# PCI_Express_Connectors.net
KiCad netlist of a schematic drawn in Altium Designer
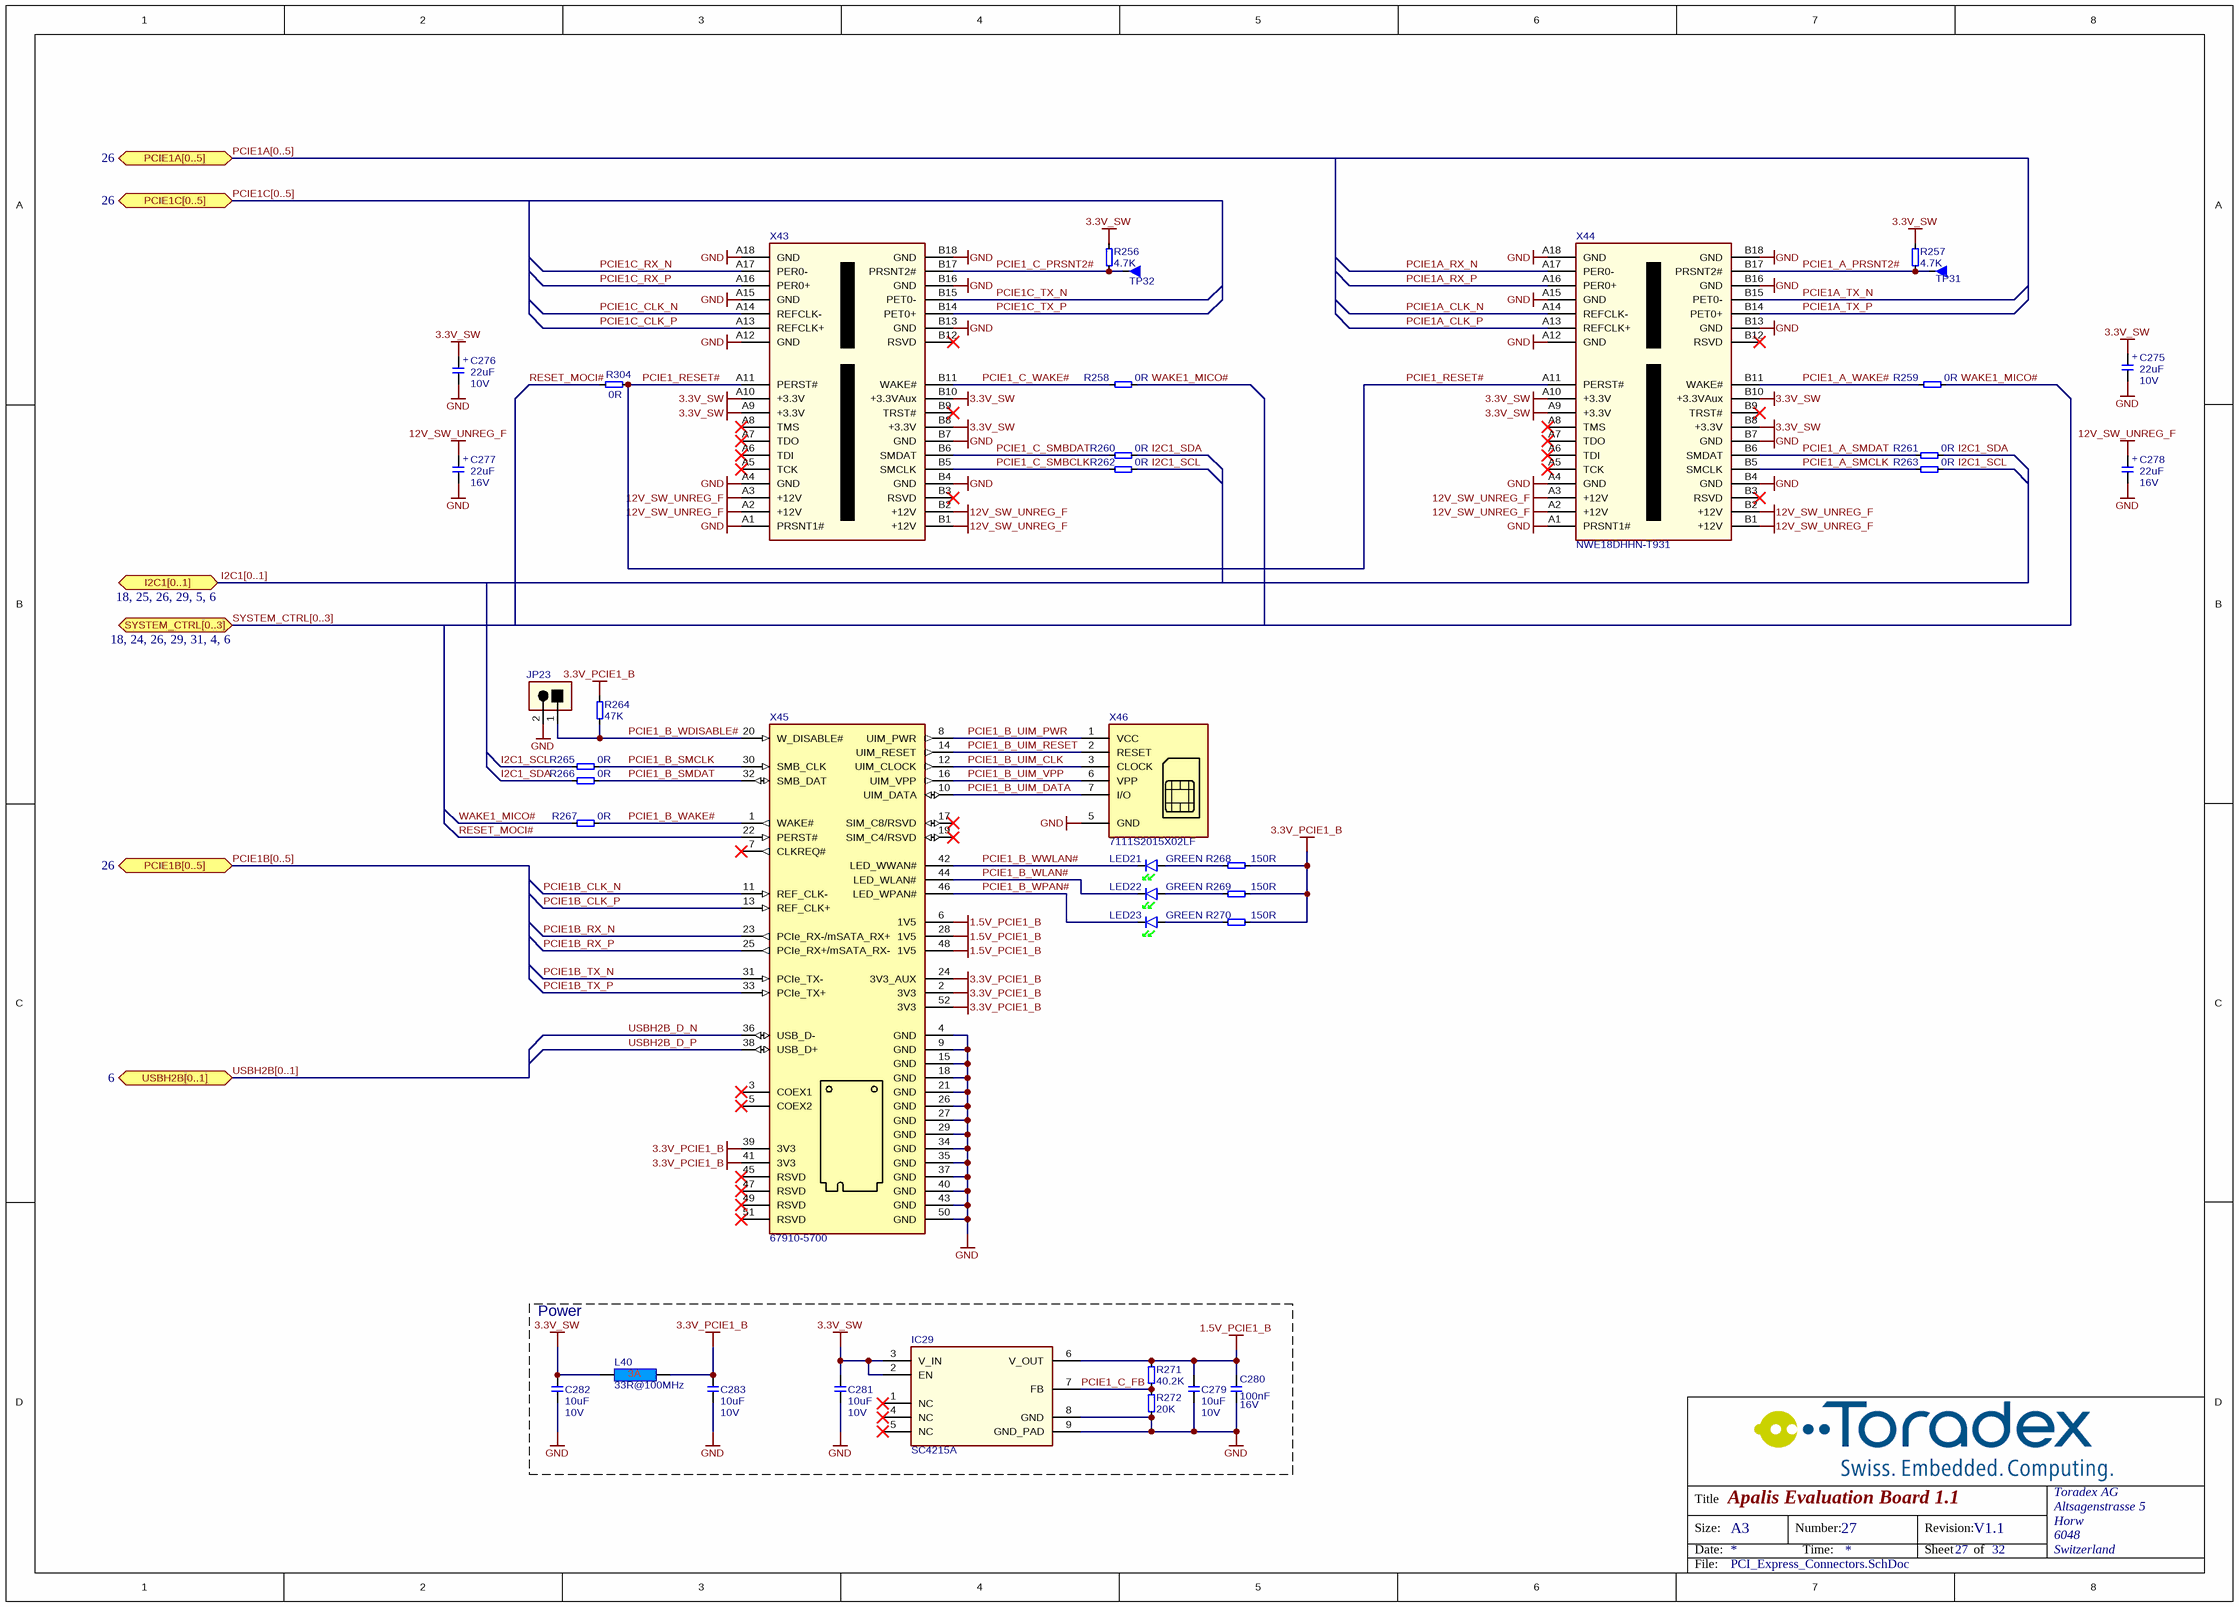
[diagram p0: PCI_Express_Connectors.SchDoc]

(export (version "E")
  (design (tool "Eeschema 10.0.6"))
  (components
    (comp (ref "C275")
      (value "22uF")
      (footprint "CAPMP3528X210N")
      (description "Capacitor TA 22uF 10V 20% 3528")
      (fields (field (name "TOLERANCE") "20%") (field (name "RATING") "10V"))
      (libsource (lib "Apalis Evaluation Board") (part "C-TA-22uF-10V-20%-3528"))
    )
    (comp (ref "C276")
      (value "22uF")
      (footprint "CAPMP3528X210N")
      (description "Capacitor TA 22uF 10V 20% 3528")
      (fields (field (name "TOLERANCE") "20%") (field (name "RATING") "10V"))
      (libsource (lib "Apalis Evaluation Board") (part "C-TA-22uF-10V-20%-3528"))
    )
    (comp (ref "C277")
      (value "22uF")
      (footprint "CAPMP3528X210N")
      (description "Capacitor TA 22uF 16V 20% 3528")
      (fields (field (name "TOLERANCE") "20%") (field (name "RATING") "16V"))
      (libsource (lib "Apalis Evaluation Board") (part "C-TA-22uF-16V-20%-3528"))
    )
    (comp (ref "C278")
      (value "22uF")
      (footprint "CAPMP3528X210N")
      (description "Capacitor TA 22uF 16V 20% 3528")
      (fields (field (name "TOLERANCE") "20%") (field (name "RATING") "16V"))
      (libsource (lib "Apalis Evaluation Board") (part "C-TA-22uF-16V-20%-3528"))
    )
    (comp (ref "C279")
      (value "10uF")
      (footprint "T_CAPC0603X33N")
      (description "Capacitor Ceramic X5R 10uF 10V 20% 0603")
      (fields (field (name "TOLERANCE") "20%") (field (name "RATING") "10V"))
      (libsource (lib "Apalis Evaluation Board") (part "C-X5R-10uF-10V-20%-0603"))
    )
    (comp (ref "C280")
      (value "100nF")
      (footprint "T_CAPC0603X33N")
      (description "Capacitor Ceramic X7R 100nF 16V 10% 0603")
      (fields (field (name "TOLERANCE") "10%") (field (name "RATING") "16V"))
      (libsource (lib "Apalis Evaluation Board") (part "C-X7R-100nF-16V-10%-0603"))
    )
    (comp (ref "C281")
      (value "10uF")
      (footprint "T_CAPC0603X33N")
      (description "Capacitor Ceramic X5R 10uF 10V 20% 0603")
      (fields (field (name "TOLERANCE") "20%") (field (name "RATING") "10V"))
      (libsource (lib "Apalis Evaluation Board") (part "C-X5R-10uF-10V-20%-0603"))
    )
    (comp (ref "C282")
      (value "10uF")
      (footprint "T_CAPC0603X33N")
      (description "Capacitor Ceramic X5R 10uF 10V 20% 0603")
      (fields (field (name "TOLERANCE") "20%") (field (name "RATING") "10V"))
      (libsource (lib "Apalis Evaluation Board") (part "C-X5R-10uF-10V-20%-0603"))
    )
    (comp (ref "C283")
      (value "10uF")
      (footprint "T_CAPC0603X33N")
      (description "Capacitor Ceramic X5R 10uF 10V 20% 0603")
      (fields (field (name "TOLERANCE") "20%") (field (name "RATING") "10V"))
      (libsource (lib "Apalis Evaluation Board") (part "C-X5R-10uF-10V-20%-0603"))
    )
    (comp (ref "IC29")
      (value "IC-Semtech-SC4215A")
      (footprint "SOIC127P650X175_HS-8N")
      (description "LDO TO 2A")
      (fields (field (name "PART NO.") "SC4215A"))
      (libsource (lib "Apalis Evaluation Board") (part "IC-Semtech-SC4215A"))
    )
    (comp (ref "JP23")
      (value "TSW-101-07-G-D")
      (footprint "T_Samtec_TSW-101-07-G-D")
      (description "Header male, 1x2 Pins, 2.54 mm pitch")
      (libsource (lib "Apalis Evaluation Board") (part "CON-Samtec-TSW-101-07-G-D"))
    )
    (comp (ref "L40")
      (value "33R@100MHz")
      (footprint "INDC1608X95N")
      (description "33R@100MHz 3A EMI FILTER")
      (fields (field (name "TOLERANCE") "25%"))
      (libsource (lib "Apalis Evaluation Board") (part "L-33R@100MHz-3A-25%-0603"))
    )
    (comp (ref "LED21")
      (value "LG T670-K1L2-1")
      (footprint "T_Osram_T670_GREEN")
      (description "LED green Osram LG T670-K1L2-1")
      (fields (field (name "COLOR") "GREEN"))
      (libsource (lib "Apalis Evaluation Board") (part "LED-Osram-T670-K1L2-1"))
    )
    (comp (ref "LED22")
      (value "LG T670-K1L2-1")
      (footprint "T_Osram_T670_GREEN")
      (description "LED green Osram LG T670-K1L2-1")
      (fields (field (name "COLOR") "GREEN"))
      (libsource (lib "Apalis Evaluation Board") (part "LED-Osram-T670-K1L2-1"))
    )
    (comp (ref "LED23")
      (value "LG T670-K1L2-1")
      (footprint "T_Osram_T670_GREEN")
      (description "LED green Osram LG T670-K1L2-1")
      (fields (field (name "COLOR") "GREEN"))
      (libsource (lib "Apalis Evaluation Board") (part "LED-Osram-T670-K1L2-1"))
    )
    (comp (ref "R256")
      (value "4.7K")
      (footprint "t_RESC0603X30N")
      (description "Resistor 4.7 Kohm 63mW 5% 0603")
      (fields (field (name "TOLERANCE") "5%"))
      (libsource (lib "Apalis Evaluation Board") (part "R-4.7kR-63mW-5%-0603"))
    )
    (comp (ref "R257")
      (value "4.7K")
      (footprint "t_RESC0603X30N")
      (description "Resistor 4.7 Kohm 63mW 5% 0603")
      (fields (field (name "TOLERANCE") "5%"))
      (libsource (lib "Apalis Evaluation Board") (part "R-4.7kR-63mW-5%-0603"))
    )
    (comp (ref "R258")
      (value "0R")
      (footprint "T_RESC0603X30N")
      (description "Resistor 0 ohm 63mW 1% 0603")
      (fields (field (name "TOLERANCE") "1%"))
      (libsource (lib "Apalis Evaluation Board") (part "R-0R-63mW-1%-0603"))
    )
    (comp (ref "R259")
      (value "0R")
      (footprint "T_RESC0603X30N")
      (description "Resistor 0 ohm 63mW 1% 0603")
      (fields (field (name "TOLERANCE") "1%"))
      (libsource (lib "Apalis Evaluation Board") (part "R-0R-63mW-1%-0603"))
    )
    (comp (ref "R260")
      (value "0R")
      (footprint "T_RESC0603X30N")
      (description "Resistor 0 ohm 63mW 1% 0603")
      (fields (field (name "TOLERANCE") "1%"))
      (libsource (lib "Apalis Evaluation Board") (part "R-0R-63mW-1%-0603"))
    )
    (comp (ref "R261")
      (value "0R")
      (footprint "T_RESC0603X30N")
      (description "Resistor 0 ohm 63mW 1% 0603")
      (fields (field (name "TOLERANCE") "1%"))
      (libsource (lib "Apalis Evaluation Board") (part "R-0R-63mW-1%-0603"))
    )
    (comp (ref "R262")
      (value "0R")
      (footprint "T_RESC0603X30N")
      (description "Resistor 0 ohm 63mW 1% 0603")
      (fields (field (name "TOLERANCE") "1%"))
      (libsource (lib "Apalis Evaluation Board") (part "R-0R-63mW-1%-0603"))
    )
    (comp (ref "R263")
      (value "0R")
      (footprint "T_RESC0603X30N")
      (description "Resistor 0 ohm 63mW 1% 0603")
      (fields (field (name "TOLERANCE") "1%"))
      (libsource (lib "Apalis Evaluation Board") (part "R-0R-63mW-1%-0603"))
    )
    (comp (ref "R264")
      (value "47K")
      (footprint "T_RESC0603X30N")
      (description "Resistor 47 Kohm 63mW 5% 0603")
      (fields (field (name "TOLERANCE") "5%"))
      (libsource (lib "Apalis Evaluation Board") (part "R-47KR-63mW-5%-0603"))
    )
    (comp (ref "R265")
      (value "0R")
      (footprint "T_RESC0603X30N")
      (description "Resistor 0 ohm 63mW 1% 0603")
      (fields (field (name "TOLERANCE") "1%"))
      (libsource (lib "Apalis Evaluation Board") (part "R-0R-63mW-1%-0603"))
    )
    (comp (ref "R266")
      (value "0R")
      (footprint "T_RESC0603X30N")
      (description "Resistor 0 ohm 63mW 1% 0603")
      (fields (field (name "TOLERANCE") "1%"))
      (libsource (lib "Apalis Evaluation Board") (part "R-0R-63mW-1%-0603"))
    )
    (comp (ref "R267")
      (value "0R")
      (footprint "T_RESC0603X30N")
      (description "Resistor 0 ohm 63mW 1% 0603")
      (fields (field (name "TOLERANCE") "1%"))
      (libsource (lib "Apalis Evaluation Board") (part "R-0R-63mW-1%-0603"))
    )
    (comp (ref "R268")
      (value "150R")
      (footprint "T_RESC0603X30N")
      (description "Resistor 150 ohm 63mW 1% 0603")
      (fields (field (name "TOLERANCE") "1%"))
      (libsource (lib "Apalis Evaluation Board") (part "R-150R-63mW-1%-0603"))
    )
    (comp (ref "R269")
      (value "150R")
      (footprint "T_RESC0603X30N")
      (description "Resistor 150 ohm 63mW 1% 0603")
      (fields (field (name "TOLERANCE") "1%"))
      (libsource (lib "Apalis Evaluation Board") (part "R-150R-63mW-1%-0603"))
    )
    (comp (ref "R270")
      (value "150R")
      (footprint "T_RESC0603X30N")
      (description "Resistor 150 ohm 63mW 1% 0603")
      (fields (field (name "TOLERANCE") "1%"))
      (libsource (lib "Apalis Evaluation Board") (part "R-150R-63mW-1%-0603"))
    )
    (comp (ref "R271")
      (value "40.2K")
      (footprint "T_RESC0603X30N")
      (description "Resistor 40.2 Kohm 63mW 1% 0603")
      (fields (field (name "TOLERANCE") "1%"))
      (libsource (lib "Apalis Evaluation Board") (part "R-40.2KR-63mW-1%-0603"))
    )
    (comp (ref "R272")
      (value "20K")
      (footprint "T_RESC0603X30N")
      (description "Resistor 20 Kohm 63mW 1% 0603")
      (fields (field (name "TOLERANCE") "1%"))
      (libsource (lib "Apalis Evaluation Board") (part "R-20KR-63mW-1%-0603"))
    )
    (comp (ref "R304")
      (value "0R")
      (footprint "T_RESC0603X30N")
      (description "Resistor 0 ohm 63mW 1% 0603")
      (fields (field (name "TOLERANCE") "1%"))
      (libsource (lib "Apalis Evaluation Board") (part "R-0R-63mW-1%-0603"))
    )
    (comp (ref "TP31")
      (value "Testpin")
      (footprint "T_TP-THT")
      (description "Testpin TH")
      (libsource (lib "Apalis Evaluation Board") (part "Testpin"))
    )
    (comp (ref "TP32")
      (value "Testpin")
      (footprint "T_TP-THT")
      (description "Testpin TH")
      (libsource (lib "Apalis Evaluation Board") (part "Testpin"))
    )
    (comp (ref "X43")
      (value "NWE18DHHN-T931")
      (footprint "T_Sullins_NWE18DHHN-T931")
      (description "PCI EXPRESS 36POS")
      (libsource (lib "") (part "CON-Sullins-NWE18DHHN-T931_1"))
    )
    (comp (ref "X44")
      (value "NWE18DHHN-T931")
      (footprint "T_Sullins_NWE18DHHN-T931")
      (description "PCI EXPRESS 36POS")
      (fields (field (name "MANUFACTURER PART NO.") "NWE18DHHN-T931"))
      (libsource (lib "Apalis Evaluation Board") (part "CON-Sullins-NWE18DHHN-T931"))
    )
    (comp (ref "X45")
      (value "67910-5700")
      (footprint "T_Molex_67910-5700")
      (description "PCIe_Mini Card Holder")
      (fields (field (name "PART NO.") "67910-5700"))
      (libsource (lib "Apalis Evaluation Board") (part "CON-Molex-67910-5700"))
    )
    (comp (ref "X46")
      (value "7111S2015X02LF")
      (footprint "T_FCI_7111S2015X02LF")
      (description "6 Contacts Sim Card Holder")
      (fields (field (name "PART NO.") "7111S2015X02LF"))
      (libsource (lib "Apalis Evaluation Board") (part "CON-FCI-7111S2015X02LF"))
    )
  )
  (nets
    (net (code "28") (name "/I2C1_SCL") (class "Default")
      (node (ref "R262") (pin "2") (pinfunction "2_2") (pintype "passive"))
      (node (ref "R263") (pin "2") (pinfunction "2_2") (pintype "passive"))
      (node (ref "R265") (pin "1") (pinfunction "1_1") (pintype "passive"))
    )
    (net (code "29") (name "/I2C1_SDA") (class "Default")
      (node (ref "R260") (pin "2") (pinfunction "2_2") (pintype "passive"))
      (node (ref "R261") (pin "2") (pinfunction "2_2") (pintype "passive"))
      (node (ref "R266") (pin "1") (pinfunction "1_1") (pintype "passive"))
    )
    (net (code "31") (name "/PCIE1A_CLK_N") (class "Default")
      (node (ref "X44") (pin "A14") (pinfunction "REFCLK-_A14") (pintype "passive"))
    )
    (net (code "32") (name "/PCIE1A_CLK_P") (class "Default")
      (node (ref "X44") (pin "A13") (pinfunction "REFCLK+_A13") (pintype "passive"))
    )
    (net (code "33") (name "/PCIE1A_RX_N") (class "Default")
      (node (ref "X44") (pin "A17") (pinfunction "PER0-_A17") (pintype "passive"))
    )
    (net (code "34") (name "/PCIE1A_RX_P") (class "Default")
      (node (ref "X44") (pin "A16") (pinfunction "PER0+_A16") (pintype "passive"))
    )
    (net (code "35") (name "/PCIE1A_TX_N") (class "Default")
      (node (ref "X44") (pin "B15") (pinfunction "PET0-_B15") (pintype "passive"))
    )
    (net (code "36") (name "/PCIE1A_TX_P") (class "Default")
      (node (ref "X44") (pin "B14") (pinfunction "PET0+_B14") (pintype "passive"))
    )
    (net (code "38") (name "/PCIE1B_CLK_N") (class "Default")
      (node (ref "X45") (pin "11") (pinfunction "REF_CLK-_11") (pintype "input"))
    )
    (net (code "39") (name "/PCIE1B_CLK_P") (class "Default")
      (node (ref "X45") (pin "13") (pinfunction "REF_CLK+_13") (pintype "input"))
    )
    (net (code "40") (name "/PCIE1B_RX_N") (class "Default")
      (node (ref "X45") (pin "23") (pinfunction "PCIe_RX-/mSATA_RX+_23") (pintype "output"))
    )
    (net (code "41") (name "/PCIE1B_RX_P") (class "Default")
      (node (ref "X45") (pin "25") (pinfunction "PCIe_RX+/mSATA_RX-_25") (pintype "output"))
    )
    (net (code "42") (name "/PCIE1B_TX_N") (class "Default")
      (node (ref "X45") (pin "31") (pinfunction "PCIe_TX-_31") (pintype "input"))
    )
    (net (code "43") (name "/PCIE1B_TX_P") (class "Default")
      (node (ref "X45") (pin "33") (pinfunction "PCIe_TX+_33") (pintype "input"))
    )
    (net (code "45") (name "/PCIE1C_CLK_N") (class "Default")
      (node (ref "X43") (pin "A14") (pinfunction "REFCLK-_A14") (pintype "passive"))
    )
    (net (code "46") (name "/PCIE1C_CLK_P") (class "Default")
      (node (ref "X43") (pin "A13") (pinfunction "REFCLK+_A13") (pintype "passive"))
    )
    (net (code "47") (name "/PCIE1C_RX_N") (class "Default")
      (node (ref "X43") (pin "A17") (pinfunction "PER0-_A17") (pintype "passive"))
    )
    (net (code "48") (name "/PCIE1C_RX_P") (class "Default")
      (node (ref "X43") (pin "A16") (pinfunction "PER0+_A16") (pintype "passive"))
    )
    (net (code "49") (name "/PCIE1C_TX_N") (class "Default")
      (node (ref "X43") (pin "B15") (pinfunction "PET0-_B15") (pintype "passive"))
    )
    (net (code "50") (name "/PCIE1C_TX_P") (class "Default")
      (node (ref "X43") (pin "B14") (pinfunction "PET0+_B14") (pintype "passive"))
    )
    (net (code "51") (name "/PCIE1_A_PRSNT2#") (class "Default")
      (node (ref "R257") (pin "1") (pinfunction "1_1") (pintype "passive"))
      (node (ref "TP31") (pin "1") (pinfunction "1_1") (pintype "passive"))
      (node (ref "X44") (pin "B17") (pinfunction "PRSNT2#_B17") (pintype "passive"))
    )
    (net (code "52") (name "/PCIE1_A_SMCLK") (class "Default")
      (node (ref "R263") (pin "1") (pinfunction "1_1") (pintype "passive"))
      (node (ref "X44") (pin "B5") (pinfunction "SMCLK_B5") (pintype "passive"))
    )
    (net (code "53") (name "/PCIE1_A_SMDAT") (class "Default")
      (node (ref "R261") (pin "1") (pinfunction "1_1") (pintype "passive"))
      (node (ref "X44") (pin "B6") (pinfunction "SMDAT_B6") (pintype "passive"))
    )
    (net (code "54") (name "/PCIE1_A_WAKE#") (class "Default")
      (node (ref "R259") (pin "1") (pinfunction "1_1") (pintype "passive"))
      (node (ref "X44") (pin "B11") (pinfunction "WAKE#_B11") (pintype "passive"))
    )
    (net (code "55") (name "/PCIE1_B_SMCLK") (class "Default")
      (node (ref "R265") (pin "2") (pinfunction "2_2") (pintype "passive"))
      (node (ref "X45") (pin "30") (pinfunction "SMB_CLK_30") (pintype "input"))
    )
    (net (code "56") (name "/PCIE1_B_SMDAT") (class "Default")
      (node (ref "R266") (pin "2") (pinfunction "2_2") (pintype "passive"))
      (node (ref "X45") (pin "32") (pinfunction "SMB_DAT_32") (pintype "bidirectional"))
    )
    (net (code "57") (name "/PCIE1_B_UIM_CLK") (class "Default")
      (node (ref "X45") (pin "12") (pinfunction "UIM_CLOCK_12") (pintype "output"))
      (node (ref "X46") (pin "3") (pinfunction "CLOCK_3") (pintype "passive"))
    )
    (net (code "58") (name "/PCIE1_B_UIM_DATA") (class "Default")
      (node (ref "X45") (pin "10") (pinfunction "UIM_DATA_10") (pintype "bidirectional"))
      (node (ref "X46") (pin "7") (pinfunction "I/O_7") (pintype "passive"))
    )
    (net (code "59") (name "/PCIE1_B_UIM_PWR") (class "Default")
      (node (ref "X45") (pin "8") (pinfunction "UIM_PWR_8") (pintype "output"))
      (node (ref "X46") (pin "1") (pinfunction "VCC_1") (pintype "passive"))
    )
    (net (code "60") (name "/PCIE1_B_UIM_RESET") (class "Default")
      (node (ref "X45") (pin "14") (pinfunction "UIM_RESET_14") (pintype "output"))
      (node (ref "X46") (pin "2") (pinfunction "RESET_2") (pintype "passive"))
    )
    (net (code "61") (name "/PCIE1_B_UIM_VPP") (class "Default")
      (node (ref "X45") (pin "16") (pinfunction "UIM_VPP_16") (pintype "output"))
      (node (ref "X46") (pin "6") (pinfunction "VPP_6") (pintype "passive"))
    )
    (net (code "62") (name "/PCIE1_B_WAKE#") (class "Default")
      (node (ref "R267") (pin "2") (pinfunction "2_2") (pintype "passive"))
      (node (ref "X45") (pin "1") (pinfunction "WAKE#_1") (pintype "output"))
    )
    (net (code "63") (name "/PCIE1_B_WDISABLE#") (class "Default")
      (node (ref "JP23") (pin "1") (pinfunction "1_1") (pintype "passive"))
      (node (ref "R264") (pin "1") (pinfunction "1_1") (pintype "passive"))
      (node (ref "X45") (pin "20") (pinfunction "W_DISABLE#_20") (pintype "input"))
    )
    (net (code "64") (name "/PCIE1_B_WLAN#") (class "Default")
      (node (ref "LED22") (pin "K") (pinfunction "K_K") (pintype "passive"))
      (node (ref "X45") (pin "44") (pinfunction "LED_WLAN#_44") (pintype "open_collector"))
    )
    (net (code "65") (name "/PCIE1_B_WPAN#") (class "Default")
      (node (ref "LED23") (pin "K") (pinfunction "K_K") (pintype "passive"))
      (node (ref "X45") (pin "46") (pinfunction "LED_WPAN#_46") (pintype "open_collector"))
    )
    (net (code "66") (name "/PCIE1_B_WWLAN#") (class "Default")
      (node (ref "LED21") (pin "K") (pinfunction "K_K") (pintype "passive"))
      (node (ref "X45") (pin "42") (pinfunction "LED_WWAN#_42") (pintype "open_collector"))
    )
    (net (code "67") (name "/PCIE1_C_FB") (class "Default")
      (node (ref "IC29") (pin "7") (pinfunction "FB_7") (pintype "passive"))
      (node (ref "R271") (pin "1") (pinfunction "1_1") (pintype "passive"))
      (node (ref "R272") (pin "2") (pinfunction "2_2") (pintype "passive"))
    )
    (net (code "68") (name "/PCIE1_C_PRSNT2#") (class "Default")
      (node (ref "R256") (pin "1") (pinfunction "1_1") (pintype "passive"))
      (node (ref "TP32") (pin "1") (pinfunction "1_1") (pintype "passive"))
      (node (ref "X43") (pin "B17") (pinfunction "PRSNT2#_B17") (pintype "passive"))
    )
    (net (code "69") (name "/PCIE1_C_SMBCLK") (class "Default")
      (node (ref "R262") (pin "1") (pinfunction "1_1") (pintype "passive"))
      (node (ref "X43") (pin "B5") (pinfunction "SMCLK_B5") (pintype "passive"))
    )
    (net (code "70") (name "/PCIE1_C_SMBDAT") (class "Default")
      (node (ref "R260") (pin "1") (pinfunction "1_1") (pintype "passive"))
      (node (ref "X43") (pin "B6") (pinfunction "SMDAT_B6") (pintype "passive"))
    )
    (net (code "71") (name "/PCIE1_C_WAKE#") (class "Default")
      (node (ref "R258") (pin "1") (pinfunction "1_1") (pintype "passive"))
      (node (ref "X43") (pin "B11") (pinfunction "WAKE#_B11") (pintype "passive"))
    )
    (net (code "72") (name "/PCIE1_RESET#") (class "Default")
      (node (ref "R304") (pin "2") (pinfunction "2_2") (pintype "passive"))
      (node (ref "X43") (pin "A11") (pinfunction "PERST#_A11") (pintype "passive"))
      (node (ref "X44") (pin "A11") (pinfunction "PERST#_A11") (pintype "passive"))
    )
    (net (code "73") (name "/RESET_MOCI#") (class "Default")
      (node (ref "R304") (pin "1") (pinfunction "1_1") (pintype "passive"))
      (node (ref "X45") (pin "22") (pinfunction "PERST#_22") (pintype "input"))
    )
    (net (code "76") (name "/USBH2B_D_N") (class "Default")
      (node (ref "X45") (pin "36") (pinfunction "USB_D-_36") (pintype "bidirectional"))
    )
    (net (code "77") (name "/USBH2B_D_P") (class "Default")
      (node (ref "X45") (pin "38") (pinfunction "USB_D+_38") (pintype "bidirectional"))
    )
    (net (code "78") (name "/WAKE1_MICO#") (class "Default")
      (node (ref "R258") (pin "2") (pinfunction "2_2") (pintype "passive"))
      (node (ref "R259") (pin "2") (pinfunction "2_2") (pintype "passive"))
      (node (ref "R267") (pin "1") (pinfunction "1_1") (pintype "passive"))
    )
    (net (code "79") (name "1.5V_PCIE1_B") (class "Default")
      (node (ref "C279") (pin "2") (pinfunction "2_2") (pintype "passive"))
      (node (ref "C280") (pin "2") (pinfunction "2_2") (pintype "passive"))
      (node (ref "IC29") (pin "6") (pinfunction "V_OUT_6") (pintype "passive"))
      (node (ref "R271") (pin "2") (pinfunction "2_2") (pintype "passive"))
      (node (ref "X45") (pin "28") (pinfunction "1V5_28") (pintype "power_in"))
      (node (ref "X45") (pin "48") (pinfunction "1V5_48") (pintype "power_in"))
      (node (ref "X45") (pin "6") (pinfunction "1V5_6") (pintype "power_in"))
    )
    (net (code "80") (name "3.3V_PCIE1_B") (class "Default")
      (node (ref "C283") (pin "2") (pinfunction "2_2") (pintype "passive"))
      (node (ref "L40") (pin "2") (pinfunction "2_2") (pintype "passive"))
      (node (ref "R264") (pin "2") (pinfunction "2_2") (pintype "passive"))
      (node (ref "R268") (pin "2") (pinfunction "2_2") (pintype "passive"))
      (node (ref "R269") (pin "2") (pinfunction "2_2") (pintype "passive"))
      (node (ref "R270") (pin "2") (pinfunction "2_2") (pintype "passive"))
      (node (ref "X45") (pin "2") (pinfunction "3V3_2") (pintype "power_in"))
      (node (ref "X45") (pin "24") (pinfunction "3V3_AUX_24") (pintype "power_in"))
      (node (ref "X45") (pin "39") (pinfunction "3V3_39") (pintype "passive"))
      (node (ref "X45") (pin "41") (pinfunction "3V3_41") (pintype "passive"))
      (node (ref "X45") (pin "52") (pinfunction "3V3_52") (pintype "power_in"))
    )
    (net (code "81") (name "3.3V_SW") (class "Default")
      (node (ref "C275") (pin "1") (pinfunction "1_1") (pintype "passive"))
      (node (ref "C276") (pin "1") (pinfunction "1_1") (pintype "passive"))
      (node (ref "C281") (pin "2") (pinfunction "2_2") (pintype "passive"))
      (node (ref "C282") (pin "2") (pinfunction "2_2") (pintype "passive"))
      (node (ref "IC29") (pin "2") (pinfunction "EN_2") (pintype "passive"))
      (node (ref "IC29") (pin "3") (pinfunction "V_IN_3") (pintype "passive"))
      (node (ref "L40") (pin "1") (pinfunction "1_1") (pintype "passive"))
      (node (ref "R256") (pin "2") (pinfunction "2_2") (pintype "passive"))
      (node (ref "R257") (pin "2") (pinfunction "2_2") (pintype "passive"))
      (node (ref "X43") (pin "A10") (pinfunction "+3.3V_A10") (pintype "passive"))
      (node (ref "X43") (pin "A9") (pinfunction "+3.3V_A9") (pintype "passive"))
      (node (ref "X43") (pin "B10") (pinfunction "+3.3VAux_B10") (pintype "passive"))
      (node (ref "X43") (pin "B8") (pinfunction "+3.3V_B8") (pintype "passive"))
      (node (ref "X44") (pin "A10") (pinfunction "+3.3V_A10") (pintype "passive"))
      (node (ref "X44") (pin "A9") (pinfunction "+3.3V_A9") (pintype "passive"))
      (node (ref "X44") (pin "B10") (pinfunction "+3.3VAux_B10") (pintype "passive"))
      (node (ref "X44") (pin "B8") (pinfunction "+3.3V_B8") (pintype "passive"))
    )
    (net (code "82") (name "12V_SW_UNREG_F") (class "Default")
      (node (ref "C277") (pin "1") (pinfunction "1_1") (pintype "passive"))
      (node (ref "C278") (pin "1") (pinfunction "1_1") (pintype "passive"))
      (node (ref "X43") (pin "A2") (pinfunction "+12V_A2") (pintype "passive"))
      (node (ref "X43") (pin "A3") (pinfunction "+12V_A3") (pintype "passive"))
      (node (ref "X43") (pin "B1") (pinfunction "+12V_B1") (pintype "passive"))
      (node (ref "X43") (pin "B2") (pinfunction "+12V_B2") (pintype "passive"))
      (node (ref "X44") (pin "A2") (pinfunction "+12V_A2") (pintype "passive"))
      (node (ref "X44") (pin "A3") (pinfunction "+12V_A3") (pintype "passive"))
      (node (ref "X44") (pin "B1") (pinfunction "+12V_B1") (pintype "passive"))
      (node (ref "X44") (pin "B2") (pinfunction "+12V_B2") (pintype "passive"))
    )
    (net (code "83") (name "GND") (class "Default")
      (node (ref "C275") (pin "2") (pinfunction "2_2") (pintype "passive"))
      (node (ref "C276") (pin "2") (pinfunction "2_2") (pintype "passive"))
      (node (ref "C277") (pin "2") (pinfunction "2_2") (pintype "passive"))
      (node (ref "C278") (pin "2") (pinfunction "2_2") (pintype "passive"))
      (node (ref "C279") (pin "1") (pinfunction "1_1") (pintype "passive"))
      (node (ref "C280") (pin "1") (pinfunction "1_1") (pintype "passive"))
      (node (ref "C281") (pin "1") (pinfunction "1_1") (pintype "passive"))
      (node (ref "C282") (pin "1") (pinfunction "1_1") (pintype "passive"))
      (node (ref "C283") (pin "1") (pinfunction "1_1") (pintype "passive"))
      (node (ref "IC29") (pin "8") (pinfunction "GND_8") (pintype "passive"))
      (node (ref "IC29") (pin "9") (pinfunction "GND_PAD_9") (pintype "passive"))
      (node (ref "JP23") (pin "2") (pinfunction "2_2") (pintype "passive"))
      (node (ref "R272") (pin "1") (pinfunction "1_1") (pintype "passive"))
      (node (ref "X43") (pin "A1") (pinfunction "PRSNT1#_A1") (pintype "passive"))
      (node (ref "X43") (pin "A12") (pinfunction "GND_A12") (pintype "passive"))
      (node (ref "X43") (pin "A15") (pinfunction "GND_A15") (pintype "passive"))
      (node (ref "X43") (pin "A18") (pinfunction "GND_A18") (pintype "passive"))
      (node (ref "X43") (pin "A4") (pinfunction "GND_A4") (pintype "passive"))
      (node (ref "X43") (pin "B13") (pinfunction "GND_B13") (pintype "passive"))
      (node (ref "X43") (pin "B16") (pinfunction "GND_B16") (pintype "passive"))
      (node (ref "X43") (pin "B18") (pinfunction "GND_B18") (pintype "passive"))
      (node (ref "X43") (pin "B4") (pinfunction "GND_B4") (pintype "passive"))
      (node (ref "X43") (pin "B7") (pinfunction "GND_B7") (pintype "passive"))
      (node (ref "X44") (pin "A1") (pinfunction "PRSNT1#_A1") (pintype "passive"))
      (node (ref "X44") (pin "A12") (pinfunction "GND_A12") (pintype "passive"))
      (node (ref "X44") (pin "A15") (pinfunction "GND_A15") (pintype "passive"))
      (node (ref "X44") (pin "A18") (pinfunction "GND_A18") (pintype "passive"))
      (node (ref "X44") (pin "A4") (pinfunction "GND_A4") (pintype "passive"))
      (node (ref "X44") (pin "B13") (pinfunction "GND_B13") (pintype "passive"))
      (node (ref "X44") (pin "B16") (pinfunction "GND_B16") (pintype "passive"))
      (node (ref "X44") (pin "B18") (pinfunction "GND_B18") (pintype "passive"))
      (node (ref "X44") (pin "B4") (pinfunction "GND_B4") (pintype "passive"))
      (node (ref "X44") (pin "B7") (pinfunction "GND_B7") (pintype "passive"))
      (node (ref "X45") (pin "15") (pinfunction "GND_15") (pintype "power_in"))
      (node (ref "X45") (pin "18") (pinfunction "GND_18") (pintype "power_in"))
      (node (ref "X45") (pin "21") (pinfunction "GND_21") (pintype "power_in"))
      (node (ref "X45") (pin "26") (pinfunction "GND_26") (pintype "power_in"))
      (node (ref "X45") (pin "27") (pinfunction "GND_27") (pintype "power_in"))
      (node (ref "X45") (pin "29") (pinfunction "GND_29") (pintype "power_in"))
      (node (ref "X45") (pin "34") (pinfunction "GND_34") (pintype "power_in"))
      (node (ref "X45") (pin "35") (pinfunction "GND_35") (pintype "power_in"))
      (node (ref "X45") (pin "37") (pinfunction "GND_37") (pintype "power_in"))
      (node (ref "X45") (pin "4") (pinfunction "GND_4") (pintype "power_in"))
      (node (ref "X45") (pin "40") (pinfunction "GND_40") (pintype "power_in"))
      (node (ref "X45") (pin "43") (pinfunction "GND_43") (pintype "power_in"))
      (node (ref "X45") (pin "50") (pinfunction "GND_50") (pintype "power_in"))
      (node (ref "X45") (pin "9") (pinfunction "GND_9") (pintype "power_in"))
      (node (ref "X46") (pin "5") (pinfunction "GND_5") (pintype "passive"))
    )
    (net (code "84") (name "Net-(LED21-PadA)") (class "Default")
      (node (ref "LED21") (pin "A") (pinfunction "A_A") (pintype "passive"))
      (node (ref "R268") (pin "1") (pinfunction "1_1") (pintype "passive"))
    )
    (net (code "85") (name "Net-(LED22-PadA)") (class "Default")
      (node (ref "LED22") (pin "A") (pinfunction "A_A") (pintype "passive"))
      (node (ref "R269") (pin "1") (pinfunction "1_1") (pintype "passive"))
    )
    (net (code "86") (name "Net-(LED23-PadA)") (class "Default")
      (node (ref "LED23") (pin "A") (pinfunction "A_A") (pintype "passive"))
      (node (ref "R270") (pin "1") (pinfunction "1_1") (pintype "passive"))
    )
    (net (code "87") (name "unconnected-(IC29-NC-Pad1)") (class "Default")
      (node (ref "IC29") (pin "1") (pinfunction "NC_1") (pintype "passive+no_connect"))
    )
    (net (code "88") (name "unconnected-(IC29-NC-Pad4)") (class "Default")
      (node (ref "IC29") (pin "4") (pinfunction "NC_4") (pintype "passive+no_connect"))
    )
    (net (code "89") (name "unconnected-(IC29-NC-Pad5)") (class "Default")
      (node (ref "IC29") (pin "5") (pinfunction "NC_5") (pintype "passive+no_connect"))
    )
    (net (code "90") (name "unconnected-(X43-RSVD-PadB3)") (class "Default")
      (node (ref "X43") (pin "B3") (pinfunction "RSVD_B3") (pintype "passive+no_connect"))
    )
    (net (code "91") (name "unconnected-(X43-RSVD-PadB12)") (class "Default")
      (node (ref "X43") (pin "B12") (pinfunction "RSVD_B12") (pintype "passive+no_connect"))
    )
    (net (code "92") (name "unconnected-(X43-TCK-PadA5)") (class "Default")
      (node (ref "X43") (pin "A5") (pinfunction "TCK_A5") (pintype "passive+no_connect"))
    )
    (net (code "93") (name "unconnected-(X43-TDI-PadA6)") (class "Default")
      (node (ref "X43") (pin "A6") (pinfunction "TDI_A6") (pintype "passive+no_connect"))
    )
    (net (code "94") (name "unconnected-(X43-TDO-PadA7)") (class "Default")
      (node (ref "X43") (pin "A7") (pinfunction "TDO_A7") (pintype "passive+no_connect"))
    )
    (net (code "95") (name "unconnected-(X43-TMS-PadA8)") (class "Default")
      (node (ref "X43") (pin "A8") (pinfunction "TMS_A8") (pintype "passive+no_connect"))
    )
    (net (code "96") (name "unconnected-(X43-TRST#-PadB9)") (class "Default")
      (node (ref "X43") (pin "B9") (pinfunction "TRST#_B9") (pintype "passive+no_connect"))
    )
    (net (code "97") (name "unconnected-(X44-RSVD-PadB3)") (class "Default")
      (node (ref "X44") (pin "B3") (pinfunction "RSVD_B3") (pintype "passive+no_connect"))
    )
    (net (code "98") (name "unconnected-(X44-RSVD-PadB12)") (class "Default")
      (node (ref "X44") (pin "B12") (pinfunction "RSVD_B12") (pintype "passive+no_connect"))
    )
    (net (code "99") (name "unconnected-(X44-TCK-PadA5)") (class "Default")
      (node (ref "X44") (pin "A5") (pinfunction "TCK_A5") (pintype "passive+no_connect"))
    )
    (net (code "100") (name "unconnected-(X44-TDI-PadA6)") (class "Default")
      (node (ref "X44") (pin "A6") (pinfunction "TDI_A6") (pintype "passive+no_connect"))
    )
    (net (code "101") (name "unconnected-(X44-TDO-PadA7)") (class "Default")
      (node (ref "X44") (pin "A7") (pinfunction "TDO_A7") (pintype "passive+no_connect"))
    )
    (net (code "102") (name "unconnected-(X44-TMS-PadA8)") (class "Default")
      (node (ref "X44") (pin "A8") (pinfunction "TMS_A8") (pintype "passive+no_connect"))
    )
    (net (code "103") (name "unconnected-(X44-TRST#-PadB9)") (class "Default")
      (node (ref "X44") (pin "B9") (pinfunction "TRST#_B9") (pintype "passive+no_connect"))
    )
    (net (code "104") (name "unconnected-(X45-CLKREQ#-Pad7)") (class "Default")
      (node (ref "X45") (pin "7") (pinfunction "CLKREQ#_7") (pintype "output+no_connect"))
    )
    (net (code "105") (name "unconnected-(X45-COEX1-Pad3)") (class "Default")
      (node (ref "X45") (pin "3") (pinfunction "COEX1_3") (pintype "passive+no_connect"))
    )
    (net (code "106") (name "unconnected-(X45-COEX2-Pad5)") (class "Default")
      (node (ref "X45") (pin "5") (pinfunction "COEX2_5") (pintype "passive+no_connect"))
    )
    (net (code "107") (name "unconnected-(X45-RSVD-Pad45)") (class "Default")
      (node (ref "X45") (pin "45") (pinfunction "RSVD_45") (pintype "passive+no_connect"))
    )
    (net (code "108") (name "unconnected-(X45-RSVD-Pad47)") (class "Default")
      (node (ref "X45") (pin "47") (pinfunction "RSVD_47") (pintype "passive+no_connect"))
    )
    (net (code "109") (name "unconnected-(X45-RSVD-Pad49)") (class "Default")
      (node (ref "X45") (pin "49") (pinfunction "RSVD_49") (pintype "passive+no_connect"))
    )
    (net (code "110") (name "unconnected-(X45-RSVD-Pad51)") (class "Default")
      (node (ref "X45") (pin "51") (pinfunction "RSVD_51") (pintype "passive+no_connect"))
    )
    (net (code "111") (name "unconnected-(X45-SIM_C4{slash}RSVD-Pad19)") (class "Default")
      (node (ref "X45") (pin "19") (pinfunction "SIM_C4/RSVD_19") (pintype "bidirectional+no_connect"))
    )
    (net (code "112") (name "unconnected-(X45-SIM_C8{slash}RSVD-Pad17)") (class "Default")
      (node (ref "X45") (pin "17") (pinfunction "SIM_C8/RSVD_17") (pintype "bidirectional+no_connect"))
    )
  )
)
